# onV1.net
KiCad netlist of a schematic drawn in Altium Designer
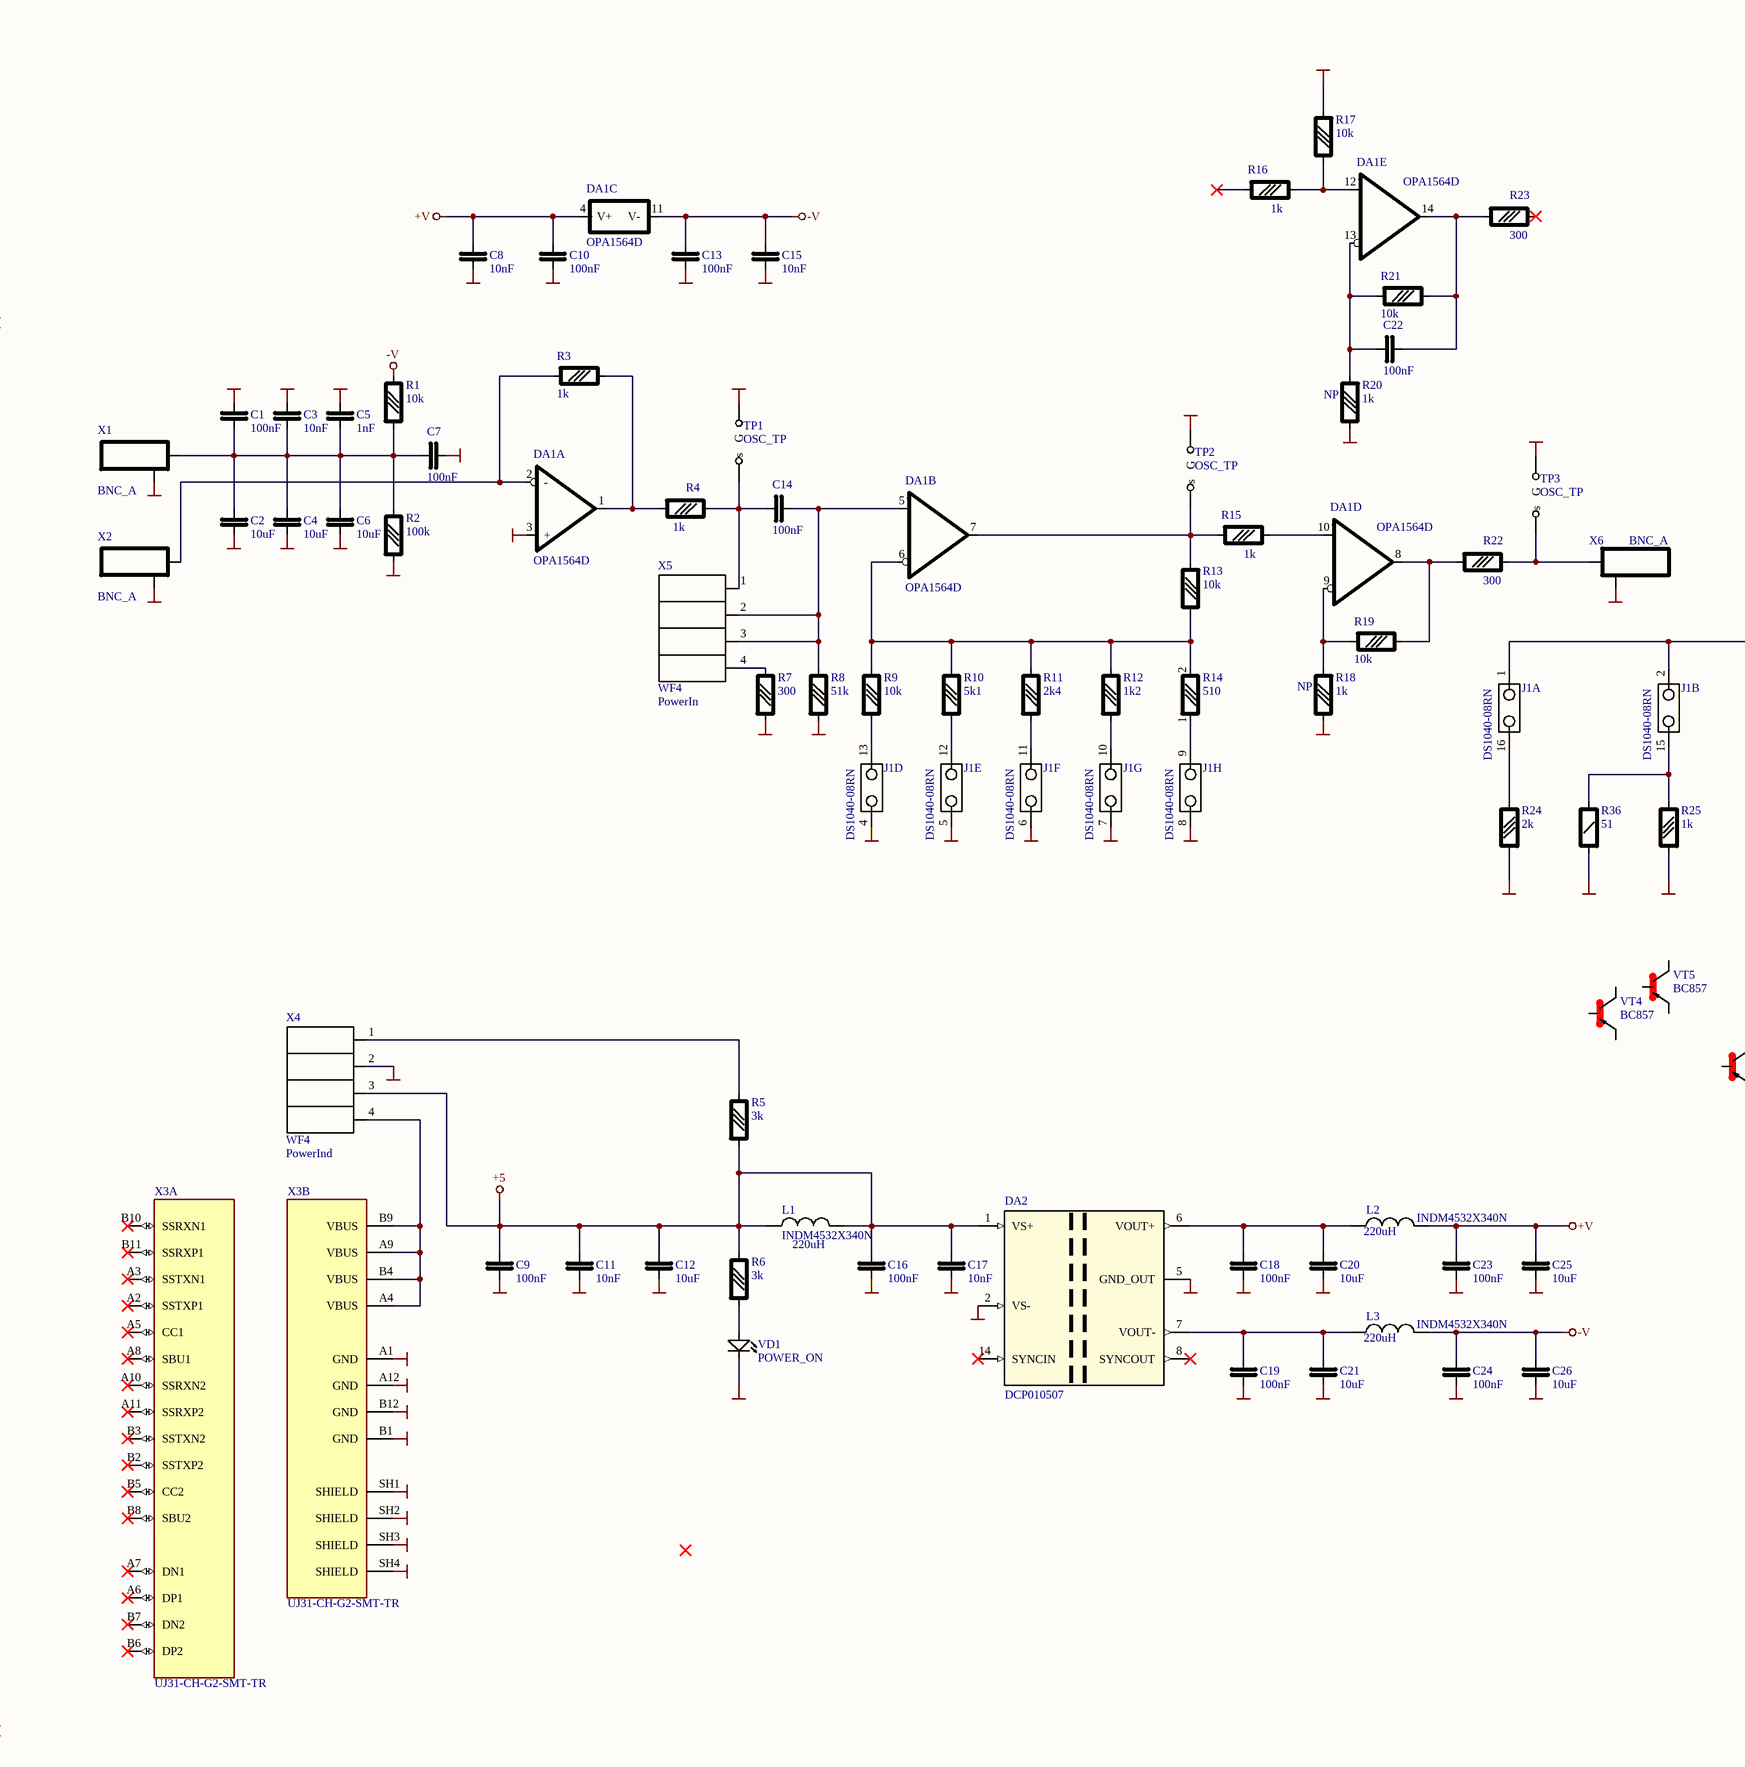
[diagram p0: onV1.SchDoc, left]
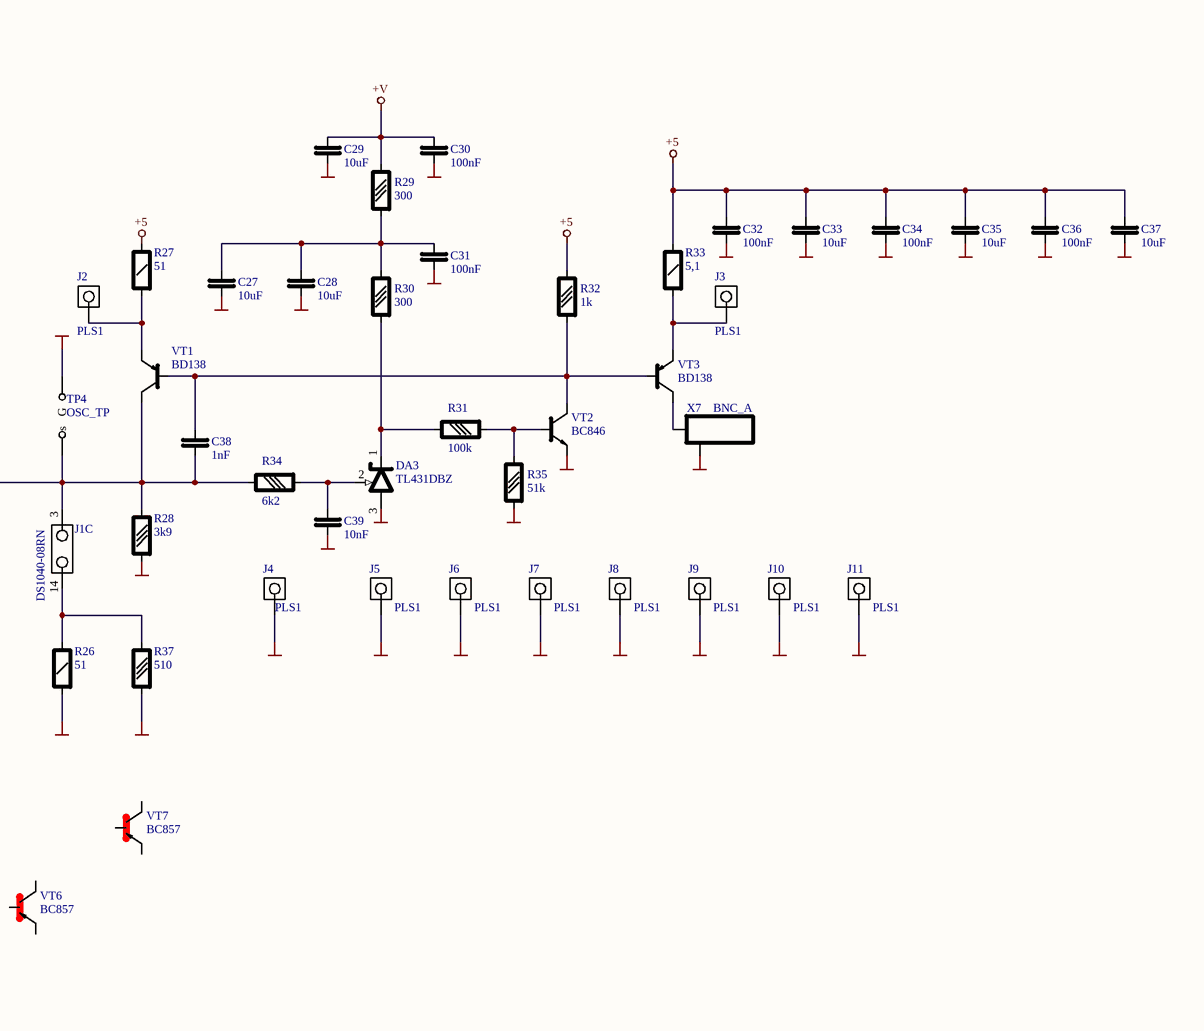
[diagram p1: onV1.SchDoc, right]

(export (version "E")
  (design (tool "Eeschema 10.0.6"))
  (components
    (comp (ref "C1")
      (value "100nF")
      (footprint "CAPC1608X87N")
      (description "Чип конденсатор 0603")
      (fields (field (name "VOLTAGE") "50V"))
      (libsource (lib "iL04_22") (part "C0603"))
    )
    (comp (ref "C2")
      (value "10uF")
      (footprint "SMD0805CAP")
      (description "Чип конденсатор 0805")
      (fields (field (name "VOLTAGE") "50V"))
      (libsource (lib "iL04_22") (part "C0805"))
    )
    (comp (ref "C3")
      (value "10nF")
      (footprint "CAPC1608X87N")
      (description "Чип конденсатор 0603")
      (fields (field (name "VOLTAGE") "50V"))
      (libsource (lib "iL04_22") (part "C0603"))
    )
    (comp (ref "C4")
      (value "10uF")
      (footprint "SMD0805CAP")
      (description "Чип конденсатор 0805")
      (fields (field (name "VOLTAGE") "50V"))
      (libsource (lib "iL04_22") (part "C0805"))
    )
    (comp (ref "C5")
      (value "1nF")
      (footprint "CAPC1608X87N")
      (description "Чип конденсатор 0603")
      (fields (field (name "VOLTAGE") "50V"))
      (libsource (lib "iL04_22") (part "C0603"))
    )
    (comp (ref "C6")
      (value "10uF")
      (footprint "SMD0805CAP")
      (description "Чип конденсатор 0805")
      (fields (field (name "VOLTAGE") "50V"))
      (libsource (lib "iL04_22") (part "C0805"))
    )
    (comp (ref "C7")
      (value "100nF")
      (footprint "CAPC1608X87N")
      (description "Чип конденсатор 0603")
      (fields (field (name "VOLTAGE") "50V"))
      (libsource (lib "iL04_22") (part "C0603"))
    )
    (comp (ref "C8")
      (value "10nF")
      (footprint "CAPC1608X87N")
      (description "Чип конденсатор 0603")
      (fields (field (name "VOLTAGE") "50V"))
      (libsource (lib "iL04_22") (part "C0603"))
    )
    (comp (ref "C9")
      (value "100nF")
      (footprint "CAPC1608X87N")
      (description "Чип конденсатор 0603")
      (fields (field (name "VOLTAGE") "50V"))
      (libsource (lib "iL04_22") (part "C0603"))
    )
    (comp (ref "C10")
      (value "100nF")
      (footprint "CAPC1608X87N")
      (description "Чип конденсатор 0603")
      (fields (field (name "VOLTAGE") "50V"))
      (libsource (lib "iL04_22") (part "C0603"))
    )
    (comp (ref "C11")
      (value "10nF")
      (footprint "CAPC1608X87N")
      (description "Чип конденсатор 0603")
      (fields (field (name "VOLTAGE") "50V"))
      (libsource (lib "iL04_22") (part "C0603"))
    )
    (comp (ref "C12")
      (value "10uF")
      (footprint "SMD0805CAP")
      (description "Чип конденсатор 0805")
      (fields (field (name "VOLTAGE") "50V"))
      (libsource (lib "iL04_22") (part "C0805"))
    )
    (comp (ref "C13")
      (value "100nF")
      (footprint "CAPC1608X87N")
      (description "Чип конденсатор 0603")
      (fields (field (name "VOLTAGE") "50V"))
      (libsource (lib "iL04_22") (part "C0603"))
    )
    (comp (ref "C14")
      (value "100nF")
      (footprint "CAPC1608X87N")
      (description "Чип конденсатор 0603")
      (fields (field (name "VOLTAGE") "50V"))
      (libsource (lib "iL04_22") (part "C0603"))
    )
    (comp (ref "C15")
      (value "10nF")
      (footprint "CAPC1608X87N")
      (description "Чип конденсатор 0603")
      (fields (field (name "VOLTAGE") "50V"))
      (libsource (lib "iL04_22") (part "C0603"))
    )
    (comp (ref "C16")
      (value "100nF")
      (footprint "CAPC1608X87N")
      (description "Чип конденсатор 0603")
      (fields (field (name "VOLTAGE") "50V"))
      (libsource (lib "iL04_22") (part "C0603"))
    )
    (comp (ref "C17")
      (value "10nF")
      (footprint "CAPC1608X87N")
      (description "Чип конденсатор 0603")
      (fields (field (name "VOLTAGE") "50V"))
      (libsource (lib "iL04_22") (part "C0603"))
    )
    (comp (ref "C18")
      (value "100nF")
      (footprint "CAPC1608X87N")
      (description "Чип конденсатор 0603")
      (fields (field (name "VOLTAGE") "50V"))
      (libsource (lib "iL04_22") (part "C0603"))
    )
    (comp (ref "C19")
      (value "100nF")
      (footprint "CAPC1608X87N")
      (description "Чип конденсатор 0603")
      (fields (field (name "VOLTAGE") "50V"))
      (libsource (lib "iL04_22") (part "C0603"))
    )
    (comp (ref "C20")
      (value "10uF")
      (footprint "SMD0805CAP")
      (description "Чип конденсатор 0805")
      (fields (field (name "VOLTAGE") "50V"))
      (libsource (lib "iL04_22") (part "C0805"))
    )
    (comp (ref "C21")
      (value "10uF")
      (footprint "SMD0805CAP")
      (description "Чип конденсатор 0805")
      (fields (field (name "VOLTAGE") "50V"))
      (libsource (lib "iL04_22") (part "C0805"))
    )
    (comp (ref "C22")
      (value "100nF")
      (footprint "CAPC1608X87N")
      (description "Чип конденсатор 0603")
      (fields (field (name "VOLTAGE") "50V"))
      (libsource (lib "iL04_22") (part "C0603"))
    )
    (comp (ref "C23")
      (value "100nF")
      (footprint "CAPC1608X87N")
      (description "Чип конденсатор 0603")
      (fields (field (name "VOLTAGE") "50V"))
      (libsource (lib "iL04_22") (part "C0603"))
    )
    (comp (ref "C24")
      (value "100nF")
      (footprint "CAPC1608X87N")
      (description "Чип конденсатор 0603")
      (fields (field (name "VOLTAGE") "50V"))
      (libsource (lib "iL04_22") (part "C0603"))
    )
    (comp (ref "C25")
      (value "10uF")
      (footprint "SMD0805CAP")
      (description "Чип конденсатор 0805")
      (fields (field (name "VOLTAGE") "50V"))
      (libsource (lib "iL04_22") (part "C0805"))
    )
    (comp (ref "C26")
      (value "10uF")
      (footprint "SMD0805CAP")
      (description "Чип конденсатор 0805")
      (fields (field (name "VOLTAGE") "50V"))
      (libsource (lib "iL04_22") (part "C0805"))
    )
    (comp (ref "C27")
      (value "10uF")
      (footprint "SMD0805CAP")
      (description "Чип конденсатор 0805")
      (fields (field (name "VOLTAGE") "50V"))
      (libsource (lib "iL04_22") (part "C0805"))
    )
    (comp (ref "C28")
      (value "10uF")
      (footprint "SMD0805CAP")
      (description "Чип конденсатор 0805")
      (fields (field (name "VOLTAGE") "50V"))
      (libsource (lib "iL04_22") (part "C0805"))
    )
    (comp (ref "C29")
      (value "10uF")
      (footprint "SMD0805CAP")
      (description "Чип конденсатор 0805")
      (fields (field (name "VOLTAGE") "50V"))
      (libsource (lib "iL04_22") (part "C0805"))
    )
    (comp (ref "C30")
      (value "100nF")
      (footprint "CAPC1608X87N")
      (description "Чип конденсатор 0603")
      (fields (field (name "VOLTAGE") "50V"))
      (libsource (lib "iL04_22") (part "C0603"))
    )
    (comp (ref "C31")
      (value "100nF")
      (footprint "CAPC1608X87N")
      (description "Чип конденсатор 0603")
      (fields (field (name "VOLTAGE") "50V"))
      (libsource (lib "iL04_22") (part "C0603"))
    )
    (comp (ref "C32")
      (value "100nF")
      (footprint "CAPC1608X87N")
      (description "Чип конденсатор 0603")
      (fields (field (name "VOLTAGE") "50V"))
      (libsource (lib "iL04_22") (part "C0603"))
    )
    (comp (ref "C33")
      (value "10uF")
      (footprint "SMD0805CAP")
      (description "Чип конденсатор 0805")
      (fields (field (name "VOLTAGE") "50V"))
      (libsource (lib "iL04_22") (part "C0805"))
    )
    (comp (ref "C34")
      (value "100nF")
      (footprint "CAPC1608X87N")
      (description "Чип конденсатор 0603")
      (fields (field (name "VOLTAGE") "50V"))
      (libsource (lib "iL04_22") (part "C0603"))
    )
    (comp (ref "C35")
      (value "10uF")
      (footprint "SMD0805CAP")
      (description "Чип конденсатор 0805")
      (fields (field (name "VOLTAGE") "50V"))
      (libsource (lib "iL04_22") (part "C0805"))
    )
    (comp (ref "C36")
      (value "100nF")
      (footprint "CAPC1608X87N")
      (description "Чип конденсатор 0603")
      (fields (field (name "VOLTAGE") "50V"))
      (libsource (lib "iL04_22") (part "C0603"))
    )
    (comp (ref "C37")
      (value "10uF")
      (footprint "SMD0805CAP")
      (description "Чип конденсатор 0805")
      (fields (field (name "VOLTAGE") "50V"))
      (libsource (lib "iL04_22") (part "C0805"))
    )
    (comp (ref "C38")
      (value "1nF")
      (footprint "CAPC1608X87N")
      (description "Чип конденсатор 0603")
      (fields (field (name "VOLTAGE") "50V"))
      (libsource (lib "iL04_22") (part "C0603"))
    )
    (comp (ref "C39")
      (value "10nF")
      (footprint "CAPC1608X87N")
      (description "Чип конденсатор 0603")
      (fields (field (name "VOLTAGE") "50V"))
      (libsource (lib "iL04_22") (part "C0603"))
    )
    (comp (ref "DA1")
      (value "OPA1564D")
      (footprint "SOIC14")
      (description "счетверённый ОУ JFED")
      (fields (field (name "VOLTAGE") "4.5V.. 36V/+-2.25..+-18V"))
      (libsource (lib "iL04_22") (part "OPA1564D"))
    )
    (comp (ref "DA2")
      (value "DCP010507")
      (footprint "NVA7")
      (description "DC/DC 5V to isolated +-7V")
      (fields (field (name "COPYRIGHT") "Copyright (C) 2022 Ultra Librarian. All rights reserved."))
      (libsource (lib "SL04_22F") (part "DCP010507"))
    )
    (comp (ref "DA3")
      (value "TL431DBZ")
      (footprint "SOT-23")
      (description "Adjustable voltage reference")
      (libsource (lib "SL04_22F") (part "TL431DBZ"))
    )
    (comp (ref "J1")
      (value "DS1040-08RN")
      (footprint "DIP16-300 W")
      (description "DIP переключатель 8x2.54")
      (libsource (lib "SL04_22F") (part "DS1040-08RN"))
    )
    (comp (ref "J2")
      (value "PLS1")
      (footprint "PLS1")
      (description "Штырь PLS1")
      (libsource (lib "iL04_22") (part "PLS1"))
    )
    (comp (ref "J3")
      (value "PLS1")
      (footprint "PLS1")
      (description "Штырь PLS1")
      (libsource (lib "iL04_22") (part "PLS1"))
    )
    (comp (ref "J4")
      (value "PLS1")
      (footprint "PLS1")
      (description "Штырь PLS1")
      (libsource (lib "iL04_22") (part "PLS1"))
    )
    (comp (ref "J5")
      (value "PLS1")
      (footprint "PLS1")
      (description "Штырь PLS1")
      (libsource (lib "iL04_22") (part "PLS1"))
    )
    (comp (ref "J6")
      (value "PLS1")
      (footprint "PLS1")
      (description "Штырь PLS1")
      (libsource (lib "iL04_22") (part "PLS1"))
    )
    (comp (ref "J7")
      (value "PLS1")
      (footprint "PLS1")
      (description "Штырь PLS1")
      (libsource (lib "iL04_22") (part "PLS1"))
    )
    (comp (ref "J8")
      (value "PLS1")
      (footprint "PLS1")
      (description "Штырь PLS1")
      (libsource (lib "iL04_22") (part "PLS1"))
    )
    (comp (ref "J9")
      (value "PLS1")
      (footprint "PLS1")
      (description "Штырь PLS1")
      (libsource (lib "iL04_22") (part "PLS1"))
    )
    (comp (ref "J10")
      (value "PLS1")
      (footprint "PLS1")
      (description "Штырь PLS1")
      (libsource (lib "iL04_22") (part "PLS1"))
    )
    (comp (ref "J11")
      (value "PLS1")
      (footprint "PLS1")
      (description "Штырь PLS1")
      (libsource (lib "iL04_22") (part "PLS1"))
    )
    (comp (ref "L1")
      (value "INDM4532X340N")
      (footprint "INDM4532X340N")
      (description "SMD Дроссель")
      (fields (field (name "INDUCTANCE") "220uH"))
      (libsource (lib "iL04_22") (part "INDM4532X340N"))
    )
    (comp (ref "L2")
      (value "INDM4532X340N")
      (footprint "INDM4532X340N")
      (description "SMD Дроссель")
      (fields (field (name "INDUCTANCE") "220uH"))
      (libsource (lib "iL04_22") (part "INDM4532X340N"))
    )
    (comp (ref "L3")
      (value "INDM4532X340N")
      (footprint "INDM4532X340N")
      (description "SMD Дроссель")
      (fields (field (name "INDUCTANCE") "220uH"))
      (libsource (lib "iL04_22") (part "INDM4532X340N"))
    )
    (comp (ref "R1")
      (value "10k")
      (footprint "RESC1608X64N")
      (description "Чип резистор 0603")
      (fields (field (name "TOLERANCE") "5%"))
      (libsource (lib "iL04_22") (part "R0603"))
    )
    (comp (ref "R2")
      (value "100k")
      (footprint "RESC1608X64N")
      (description "Чип резистор 0603")
      (fields (field (name "TOLERANCE") "5%"))
      (libsource (lib "iL04_22") (part "R0603"))
    )
    (comp (ref "R3")
      (value "1k")
      (footprint "RESC1608X64N")
      (description "Чип резистор 0603")
      (fields (field (name "TOLERANCE") "5%"))
      (libsource (lib "iL04_22") (part "R0603"))
    )
    (comp (ref "R4")
      (value "1k")
      (footprint "RESC1608X64N")
      (description "Чип резистор 0603")
      (fields (field (name "TOLERANCE") "5%"))
      (libsource (lib "iL04_22") (part "R0603"))
    )
    (comp (ref "R5")
      (value "3k")
      (footprint "RESC1608X64N")
      (description "Чип резистор 0603")
      (fields (field (name "TOLERANCE") "5%"))
      (libsource (lib "iL04_22") (part "R0603"))
    )
    (comp (ref "R6")
      (value "3k")
      (footprint "RESC1608X64N")
      (description "Чип резистор 0603")
      (fields (field (name "TOLERANCE") "5%"))
      (libsource (lib "iL04_22") (part "R0603"))
    )
    (comp (ref "R7")
      (value "300")
      (footprint "RESC1608X64N")
      (description "Чип резистор 0603")
      (fields (field (name "TOLERANCE") "5%"))
      (libsource (lib "iL04_22") (part "R0603"))
    )
    (comp (ref "R8")
      (value "51k")
      (footprint "RESC1608X64N")
      (description "Чип резистор 0603")
      (fields (field (name "TOLERANCE") "5%"))
      (libsource (lib "iL04_22") (part "R0603"))
    )
    (comp (ref "R9")
      (value "10k")
      (footprint "RESC1608X64N")
      (description "Чип резистор 0603")
      (fields (field (name "TOLERANCE") "5%"))
      (libsource (lib "iL04_22") (part "R0603"))
    )
    (comp (ref "R10")
      (value "5k1")
      (footprint "RESC1608X64N")
      (description "Чип резистор 0603")
      (fields (field (name "TOLERANCE") "5%"))
      (libsource (lib "iL04_22") (part "R0603"))
    )
    (comp (ref "R11")
      (value "2k4")
      (footprint "RESC1608X64N")
      (description "Чип резистор 0603")
      (fields (field (name "TOLERANCE") "5%"))
      (libsource (lib "iL04_22") (part "R0603"))
    )
    (comp (ref "R12")
      (value "1k2")
      (footprint "RESC1608X64N")
      (description "Чип резистор 0603")
      (fields (field (name "TOLERANCE") "5%"))
      (libsource (lib "iL04_22") (part "R0603"))
    )
    (comp (ref "R13")
      (value "10k")
      (footprint "RESC1608X64N")
      (description "Чип резистор 0603")
      (fields (field (name "TOLERANCE") "5%"))
      (libsource (lib "iL04_22") (part "R0603"))
    )
    (comp (ref "R14")
      (value "510")
      (footprint "RESC1608X64N")
      (description "Чип резистор 0603")
      (fields (field (name "TOLERANCE") "5%"))
      (libsource (lib "") (part "R0603_1"))
    )
    (comp (ref "R15")
      (value "1k")
      (footprint "RESC1608X64N")
      (description "Чип резистор 0603")
      (fields (field (name "TOLERANCE") "5%"))
      (libsource (lib "iL04_22") (part "R0603"))
    )
    (comp (ref "R16")
      (value "1k")
      (footprint "RESC1608X64N")
      (description "Чип резистор 0603")
      (fields (field (name "TOLERANCE") "5%"))
      (libsource (lib "iL04_22") (part "R0603"))
    )
    (comp (ref "R17")
      (value "10k")
      (footprint "RESC1608X64N")
      (description "Чип резистор 0603")
      (fields (field (name "TOLERANCE") "5%"))
      (libsource (lib "iL04_22") (part "R0603"))
    )
    (comp (ref "R18")
      (value "1k")
      (footprint "RESC1608X64N")
      (description "Чип резистор 0603")
      (fields (field (name "TOLERANCE") "5%") (field (name "SOLDEROPTION") "NP"))
      (libsource (lib "iL04_22") (part "R0603"))
    )
    (comp (ref "R19")
      (value "10k")
      (footprint "RESC1608X64N")
      (description "Чип резистор 0603")
      (fields (field (name "TOLERANCE") "5%"))
      (libsource (lib "iL04_22") (part "R0603"))
    )
    (comp (ref "R20")
      (value "1k")
      (footprint "RESC1608X64N")
      (description "Чип резистор 0603")
      (fields (field (name "TOLERANCE") "5%") (field (name "SOLDEROPTION") "NP"))
      (libsource (lib "iL04_22") (part "R0603"))
    )
    (comp (ref "R21")
      (value "10k")
      (footprint "RESC1608X64N")
      (description "Чип резистор 0603")
      (fields (field (name "TOLERANCE") "5%"))
      (libsource (lib "iL04_22") (part "R0603"))
    )
    (comp (ref "R22")
      (value "300")
      (footprint "RESC1608X64N")
      (description "Чип резистор 0603")
      (fields (field (name "TOLERANCE") "5%"))
      (libsource (lib "iL04_22") (part "R0603"))
    )
    (comp (ref "R23")
      (value "300")
      (footprint "RESC1608X64N")
      (description "Чип резистор 0603")
      (fields (field (name "TOLERANCE") "5%"))
      (libsource (lib "iL04_22") (part "R0603"))
    )
    (comp (ref "R24")
      (value "2k")
      (footprint "RESC1608X64N")
      (description "Чип резистор 0603")
      (fields (field (name "TOLERANCE") "5%"))
      (libsource (lib "iL04_22") (part "R0603"))
    )
    (comp (ref "R25")
      (value "1k")
      (footprint "RESC1608X64N")
      (description "Чип резистор 0603")
      (fields (field (name "TOLERANCE") "5%"))
      (libsource (lib "iL04_22") (part "R0603"))
    )
    (comp (ref "R26")
      (value "51")
      (footprint "RES1206")
      (description "Чип резистор 1206")
      (fields (field (name "TOLERANCE") "5%"))
      (libsource (lib "iL04_22") (part "R1206"))
    )
    (comp (ref "R27")
      (value "51")
      (footprint "RES1206")
      (description "Чип резистор 1206")
      (fields (field (name "TOLERANCE") "5%"))
      (libsource (lib "iL04_22") (part "R1206"))
    )
    (comp (ref "R28")
      (value "3k9")
      (footprint "RESC1608X64N")
      (description "Чип резистор 0603")
      (fields (field (name "TOLERANCE") "5%"))
      (libsource (lib "iL04_22") (part "R0603"))
    )
    (comp (ref "R29")
      (value "300")
      (footprint "RESC1608X64N")
      (description "Чип резистор 0603")
      (fields (field (name "TOLERANCE") "5%"))
      (libsource (lib "iL04_22") (part "R0603"))
    )
    (comp (ref "R30")
      (value "300")
      (footprint "RESC1608X64N")
      (description "Чип резистор 0603")
      (fields (field (name "TOLERANCE") "5%"))
      (libsource (lib "iL04_22") (part "R0603"))
    )
    (comp (ref "R31")
      (value "100k")
      (footprint "RESC1608X64N")
      (description "Чип резистор 0603")
      (fields (field (name "TOLERANCE") "5%"))
      (libsource (lib "iL04_22") (part "R0603"))
    )
    (comp (ref "R32")
      (value "1k")
      (footprint "RESC1608X64N")
      (description "Чип резистор 0603")
      (fields (field (name "TOLERANCE") "5%"))
      (libsource (lib "iL04_22") (part "R0603"))
    )
    (comp (ref "R33")
      (value "5,1")
      (footprint "RES1206")
      (description "Чип резистор 1206")
      (fields (field (name "TOLERANCE") "5%"))
      (libsource (lib "iL04_22") (part "R1206"))
    )
    (comp (ref "R34")
      (value "6k2")
      (footprint "RESC1608X64N")
      (description "Чип резистор 0603")
      (fields (field (name "TOLERANCE") "5%"))
      (libsource (lib "iL04_22") (part "R0603"))
    )
    (comp (ref "R35")
      (value "51k")
      (footprint "RESC1608X64N")
      (description "Чип резистор 0603")
      (fields (field (name "TOLERANCE") "5%"))
      (libsource (lib "iL04_22") (part "R0603"))
    )
    (comp (ref "R36")
      (value "51")
      (footprint "RES1206")
      (description "Чип резистор 1206")
      (fields (field (name "TOLERANCE") "5%"))
      (libsource (lib "iL04_22") (part "R1206"))
    )
    (comp (ref "R37")
      (value "510")
      (footprint "RESC1608X64N")
      (description "Чип резистор 0603")
      (fields (field (name "TOLERANCE") "5%"))
      (libsource (lib "iL04_22") (part "R0603"))
    )
    (comp (ref "TP1")
      (value "OSC_TP")
      (footprint "TP2")
      (description "Контрольная точка для подключения осциллографа короткой землёй")
      (libsource (lib "iL04_22") (part "OscTP"))
    )
    (comp (ref "TP2")
      (value "OSC_TP")
      (footprint "TP2")
      (description "Контрольная точка для подключения осциллографа короткой землёй")
      (libsource (lib "iL04_22") (part "OscTP"))
    )
    (comp (ref "TP3")
      (value "OSC_TP")
      (footprint "TP2")
      (description "Контрольная точка для подключения осциллографа короткой землёй")
      (libsource (lib "iL04_22") (part "OscTP"))
    )
    (comp (ref "TP4")
      (value "OSC_TP")
      (footprint "TP2")
      (description "Контрольная точка для подключения осциллографа короткой землёй")
      (libsource (lib "iL04_22") (part "OscTP"))
    )
    (comp (ref "VD1")
      (value "POWER_ON")
      (footprint "LED0603")
      (description "Чип светодиод 0603")
      (libsource (lib "iL04_22") (part "LED0603"))
    )
    (comp (ref "VT1")
      (value "BD138")
      (footprint "TO229P780X300X1364-3")
      (description "PNP  средней мощности (КГ814)")
      (fields (field (name "VOLTAGE") "40-100"))
      (libsource (lib "iL04_22") (part "BD138"))
    )
    (comp (ref "VT2")
      (value "BC846")
      (footprint "SOT-23")
      (description "NPN транзистор")
      (fields (field (name "VOLTAGE") "65V"))
      (libsource (lib "iL04_22") (part "BC846"))
    )
    (comp (ref "VT3")
      (value "BD138")
      (footprint "TO229P780X300X1364-3")
      (description "PNP  средней мощности (КГ814)")
      (fields (field (name "VOLTAGE") "40-100"))
      (libsource (lib "iL04_22") (part "BD138"))
    )
    (comp (ref "VT4")
      (value "BC857")
      (footprint "SOT-23")
      (description "PNP транзистор")
      (fields (field (name "VOLTAGE") "65V"))
      (libsource (lib "SL04_22F") (part "BC857"))
    )
    (comp (ref "VT5")
      (value "BC857")
      (footprint "SOT-23")
      (description "PNP транзистор")
      (fields (field (name "VOLTAGE") "65V"))
      (libsource (lib "SL04_22F") (part "BC857"))
    )
    (comp (ref "VT6")
      (value "BC857")
      (footprint "SOT-23")
      (description "PNP транзистор")
      (fields (field (name "VOLTAGE") "65V"))
      (libsource (lib "SL04_22F") (part "BC857"))
    )
    (comp (ref "VT7")
      (value "BC857")
      (footprint "SOT-23")
      (description "PNP транзистор")
      (fields (field (name "VOLTAGE") "65V"))
      (libsource (lib "SL04_22F") (part "BC857"))
    )
    (comp (ref "X1")
      (value "BNC_A")
      (footprint "TYCO_1-1337542-0")
      (description "BNC розетка")
      (fields (field (name "PARTNUM") "TYCO_1-1337542-0"))
      (libsource (lib "iL04_22") (part "BNC_A"))
    )
    (comp (ref "X2")
      (value "BNC_A")
      (footprint "TYCO_1-1337542-0")
      (description "BNC розетка")
      (fields (field (name "PARTNUM") "TYCO_1-1337542-0"))
      (libsource (lib "iL04_22") (part "BNC_A"))
    )
    (comp (ref "X3")
      (value "UJ31-CH-G2-SMT-TR")
      (footprint "CUI_UJ31-CH-G2-SMT-TR")
      (description "Type C, USB 3.1 Gen 2, 5 A, Right Angle, Surface Mount (SMT), USB Receptacle")
      (fields (field (name "MF") "CUI Devices"))
      (libsource (lib "SL04_22F") (part "UJ31-CH-G2-SMT-TR"))
    )
    (comp (ref "X4")
      (value "WF4")
      (footprint "MOLEX_22-27-2041")
      (description "Вилка  WF4x2.54")
      (fields (field (name "CONNECTTO") "PowerInd"))
      (libsource (lib "iL04_22") (part "WF4"))
    )
    (comp (ref "X5")
      (value "WF4")
      (footprint "MOLEX_22-27-2041")
      (description "Вилка  WF4x2.54")
      (fields (field (name "CONNECTTO") "PowerIn"))
      (libsource (lib "iL04_22") (part "WF4"))
    )
    (comp (ref "X6")
      (value "BNC_A")
      (footprint "TYCO_1-1337542-0")
      (description "BNC розетка")
      (fields (field (name "PARTNUM") "TYCO_1-1337542-0"))
      (libsource (lib "iL04_22") (part "BNC_A"))
    )
    (comp (ref "X7")
      (value "BNC_A")
      (footprint "TYCO_1-1337542-0")
      (description "BNC розетка")
      (fields (field (name "PARTNUM") "TYCO_1-1337542-0"))
      (libsource (lib "iL04_22") (part "BNC_A"))
    )
  )
  (nets
    (net (code "1") (name "+5") (class "Default")
      (node (ref "C11") (pin "2") (pinfunction "2_2") (pintype "passive"))
      (node (ref "C12") (pin "2") (pinfunction "2_2") (pintype "passive"))
      (node (ref "C16") (pin "2") (pinfunction "2_2") (pintype "passive"))
      (node (ref "C17") (pin "2") (pinfunction "2_2") (pintype "passive"))
      (node (ref "C32") (pin "2") (pinfunction "2_2") (pintype "passive"))
      (node (ref "C33") (pin "2") (pinfunction "2_2") (pintype "passive"))
      (node (ref "C34") (pin "2") (pinfunction "2_2") (pintype "passive"))
      (node (ref "C35") (pin "2") (pinfunction "2_2") (pintype "passive"))
      (node (ref "C36") (pin "2") (pinfunction "2_2") (pintype "passive"))
      (node (ref "C37") (pin "2") (pinfunction "2_2") (pintype "passive"))
      (node (ref "C9") (pin "2") (pinfunction "2_2") (pintype "passive"))
      (node (ref "DA2") (pin "1") (pinfunction "VS+_1") (pintype "input"))
      (node (ref "L1") (pin "1") (pinfunction "1_1") (pintype "passive"))
      (node (ref "L1") (pin "2") (pinfunction "2_2") (pintype "passive"))
      (node (ref "R27") (pin "2") (pinfunction "2_2") (pintype "passive"))
      (node (ref "R32") (pin "2") (pinfunction "2_2") (pintype "passive"))
      (node (ref "R33") (pin "2") (pinfunction "2_2") (pintype "passive"))
      (node (ref "R5") (pin "1") (pinfunction "1_1") (pintype "passive"))
      (node (ref "R6") (pin "2") (pinfunction "2_2") (pintype "passive"))
      (node (ref "X4") (pin "3") (pinfunction "3_3") (pintype "passive"))
    )
    (net (code "2") (name "+V") (class "Default")
      (node (ref "C10") (pin "2") (pinfunction "2_2") (pintype "passive"))
      (node (ref "C23") (pin "2") (pinfunction "2_2") (pintype "passive"))
      (node (ref "C25") (pin "2") (pinfunction "2_2") (pintype "passive"))
      (node (ref "C29") (pin "2") (pinfunction "2_2") (pintype "passive"))
      (node (ref "C30") (pin "2") (pinfunction "2_2") (pintype "passive"))
      (node (ref "C8") (pin "2") (pinfunction "2_2") (pintype "passive"))
      (node (ref "DA1") (pin "4") (pinfunction "V+_4") (pintype "power_in"))
      (node (ref "L2") (pin "2") (pinfunction "2_2") (pintype "passive"))
      (node (ref "R29") (pin "2") (pinfunction "2_2") (pintype "passive"))
    )
    (net (code "3") (name "-V") (class "Default")
      (node (ref "C13") (pin "2") (pinfunction "2_2") (pintype "passive"))
      (node (ref "C15") (pin "2") (pinfunction "2_2") (pintype "passive"))
      (node (ref "C24") (pin "2") (pinfunction "2_2") (pintype "passive"))
      (node (ref "C26") (pin "2") (pinfunction "2_2") (pintype "passive"))
      (node (ref "DA1") (pin "11") (pinfunction "V-_11") (pintype "power_in"))
      (node (ref "L3") (pin "2") (pinfunction "2_2") (pintype "passive"))
      (node (ref "R1") (pin "2") (pinfunction "2_2") (pintype "passive"))
    )
    (net (code "4") (name "GND") (class "Default")
      (node (ref "C1") (pin "2") (pinfunction "2_2") (pintype "passive"))
      (node (ref "C10") (pin "1") (pinfunction "1_1") (pintype "passive"))
      (node (ref "C11") (pin "1") (pinfunction "1_1") (pintype "passive"))
      (node (ref "C12") (pin "1") (pinfunction "1_1") (pintype "passive"))
      (node (ref "C13") (pin "1") (pinfunction "1_1") (pintype "passive"))
      (node (ref "C15") (pin "1") (pinfunction "1_1") (pintype "passive"))
      (node (ref "C16") (pin "1") (pinfunction "1_1") (pintype "passive"))
      (node (ref "C17") (pin "1") (pinfunction "1_1") (pintype "passive"))
      (node (ref "C18") (pin "1") (pinfunction "1_1") (pintype "passive"))
      (node (ref "C19") (pin "1") (pinfunction "1_1") (pintype "passive"))
      (node (ref "C2") (pin "1") (pinfunction "1_1") (pintype "passive"))
      (node (ref "C20") (pin "1") (pinfunction "1_1") (pintype "passive"))
      (node (ref "C21") (pin "1") (pinfunction "1_1") (pintype "passive"))
      (node (ref "C23") (pin "1") (pinfunction "1_1") (pintype "passive"))
      (node (ref "C24") (pin "1") (pinfunction "1_1") (pintype "passive"))
      (node (ref "C25") (pin "1") (pinfunction "1_1") (pintype "passive"))
      (node (ref "C26") (pin "1") (pinfunction "1_1") (pintype "passive"))
      (node (ref "C27") (pin "1") (pinfunction "1_1") (pintype "passive"))
      (node (ref "C28") (pin "1") (pinfunction "1_1") (pintype "passive"))
      (node (ref "C29") (pin "1") (pinfunction "1_1") (pintype "passive"))
      (node (ref "C3") (pin "2") (pinfunction "2_2") (pintype "passive"))
      (node (ref "C30") (pin "1") (pinfunction "1_1") (pintype "passive"))
      (node (ref "C31") (pin "1") (pinfunction "1_1") (pintype "passive"))
      (node (ref "C32") (pin "1") (pinfunction "1_1") (pintype "passive"))
      (node (ref "C33") (pin "1") (pinfunction "1_1") (pintype "passive"))
      (node (ref "C34") (pin "1") (pinfunction "1_1") (pintype "passive"))
      (node (ref "C35") (pin "1") (pinfunction "1_1") (pintype "passive"))
      (node (ref "C36") (pin "1") (pinfunction "1_1") (pintype "passive"))
      (node (ref "C37") (pin "1") (pinfunction "1_1") (pintype "passive"))
      (node (ref "C39") (pin "1") (pinfunction "1_1") (pintype "passive"))
      (node (ref "C4") (pin "1") (pinfunction "1_1") (pintype "passive"))
      (node (ref "C5") (pin "2") (pinfunction "2_2") (pintype "passive"))
      (node (ref "C6") (pin "1") (pinfunction "1_1") (pintype "passive"))
      (node (ref "C7") (pin "2") (pinfunction "2_2") (pintype "passive"))
      (node (ref "C8") (pin "1") (pinfunction "1_1") (pintype "passive"))
      (node (ref "C9") (pin "1") (pinfunction "1_1") (pintype "passive"))
      (node (ref "DA1") (pin "3") (pinfunction "+_3") (pintype "input"))
      (node (ref "DA2") (pin "2") (pinfunction "VS-_2") (pintype "input"))
      (node (ref "DA2") (pin "5") (pinfunction "GND_OUT_5") (pintype "power_in"))
      (node (ref "DA3") (pin "3") (pinfunction "A_3") (pintype "passive"))
      (node (ref "J1") (pin "4") (pinfunction "4_4") (pintype "passive"))
      (node (ref "J1") (pin "5") (pinfunction "5_5") (pintype "passive"))
      (node (ref "J1") (pin "6") (pinfunction "6_6") (pintype "passive"))
      (node (ref "J1") (pin "7") (pinfunction "7_7") (pintype "passive"))
      (node (ref "J1") (pin "8") (pinfunction "8_8") (pintype "passive"))
      (node (ref "J10") (pin "1") (pinfunction "1_1") (pintype "passive"))
      (node (ref "J11") (pin "1") (pinfunction "1_1") (pintype "passive"))
      (node (ref "J4") (pin "1") (pinfunction "1_1") (pintype "passive"))
      (node (ref "J5") (pin "1") (pinfunction "1_1") (pintype "passive"))
      (node (ref "J6") (pin "1") (pinfunction "1_1") (pintype "passive"))
      (node (ref "J7") (pin "1") (pinfunction "1_1") (pintype "passive"))
      (node (ref "J8") (pin "1") (pinfunction "1_1") (pintype "passive"))
      (node (ref "J9") (pin "1") (pinfunction "1_1") (pintype "passive"))
      (node (ref "R17") (pin "1") (pinfunction "1_1") (pintype "passive"))
      (node (ref "R18") (pin "2") (pinfunction "2_2") (pintype "passive"))
      (node (ref "R2") (pin "1") (pinfunction "1_1") (pintype "passive"))
      (node (ref "R20") (pin "2") (pinfunction "2_2") (pintype "passive"))
      (node (ref "R24") (pin "1") (pinfunction "1_1") (pintype "passive"))
      (node (ref "R25") (pin "1") (pinfunction "1_1") (pintype "passive"))
      (node (ref "R26") (pin "1") (pinfunction "1_1") (pintype "passive"))
      (node (ref "R28") (pin "1") (pinfunction "1_1") (pintype "passive"))
      (node (ref "R35") (pin "1") (pinfunction "1_1") (pintype "passive"))
      (node (ref "R36") (pin "1") (pinfunction "1_1") (pintype "passive"))
      (node (ref "R37") (pin "1") (pinfunction "1_1") (pintype "passive"))
      (node (ref "R7") (pin "1") (pinfunction "1_1") (pintype "passive"))
      (node (ref "R8") (pin "1") (pinfunction "1_1") (pintype "passive"))
      (node (ref "TP1") (pin "2") (pinfunction "G_2") (pintype "passive"))
      (node (ref "TP2") (pin "2") (pinfunction "G_2") (pintype "passive"))
      (node (ref "TP3") (pin "2") (pinfunction "G_2") (pintype "passive"))
      (node (ref "TP4") (pin "2") (pinfunction "G_2") (pintype "passive"))
      (node (ref "VD1") (pin "1") (pinfunction "Cathode_1") (pintype "passive"))
      (node (ref "VT2") (pin "2") (pinfunction "Emitter_2") (pintype "passive"))
      (node (ref "X1") (pin "2") (pinfunction "2_2") (pintype "passive"))
      (node (ref "X2") (pin "2") (pinfunction "2_2") (pintype "passive"))
      (node (ref "X3") (pin "A1") (pinfunction "GND_A1") (pintype "power_in"))
      (node (ref "X3") (pin "A12") (pinfunction "GND_A12") (pintype "power_in"))
      (node (ref "X3") (pin "B1") (pinfunction "GND_B1") (pintype "power_in"))
      (node (ref "X3") (pin "B12") (pinfunction "GND_B12") (pintype "power_in"))
      (node (ref "X3") (pin "SH1") (pinfunction "SHIELD_SH1") (pintype "power_in"))
      (node (ref "X3") (pin "SH2") (pinfunction "SHIELD_SH2") (pintype "power_in"))
      (node (ref "X3") (pin "SH3") (pinfunction "SHIELD_SH3") (pintype "power_in"))
      (node (ref "X3") (pin "SH4") (pinfunction "SHIELD_SH4") (pintype "power_in"))
      (node (ref "X4") (pin "2") (pinfunction "2_2") (pintype "passive"))
      (node (ref "X6") (pin "2") (pinfunction "2_2") (pintype "passive"))
      (node (ref "X7") (pin "2") (pinfunction "2_2") (pintype "passive"))
    )
    (net (code "5") (name "Net-(C1-Pad1)") (class "Default")
      (node (ref "C1") (pin "1") (pinfunction "1_1") (pintype "passive"))
      (node (ref "C2") (pin "2") (pinfunction "2_2") (pintype "passive"))
      (node (ref "C3") (pin "1") (pinfunction "1_1") (pintype "passive"))
      (node (ref "C4") (pin "2") (pinfunction "2_2") (pintype "passive"))
      (node (ref "C5") (pin "1") (pinfunction "1_1") (pintype "passive"))
      (node (ref "C6") (pin "2") (pinfunction "2_2") (pintype "passive"))
      (node (ref "C7") (pin "1") (pinfunction "1_1") (pintype "passive"))
      (node (ref "R1") (pin "1") (pinfunction "1_1") (pintype "passive"))
      (node (ref "R2") (pin "2") (pinfunction "2_2") (pintype "passive"))
      (node (ref "X1") (pin "1") (pinfunction "1_1") (pintype "passive"))
    )
    (net (code "6") (name "Net-(C27-Pad2)") (class "Default")
      (node (ref "C27") (pin "2") (pinfunction "2_2") (pintype "passive"))
      (node (ref "C28") (pin "2") (pinfunction "2_2") (pintype "passive"))
      (node (ref "C31") (pin "2") (pinfunction "2_2") (pintype "passive"))
      (node (ref "R29") (pin "1") (pinfunction "1_1") (pintype "passive"))
      (node (ref "R30") (pin "2") (pinfunction "2_2") (pintype "passive"))
    )
    (net (code "7") (name "Net-(DA1A--)") (class "Default")
      (node (ref "DA1") (pin "2") (pinfunction "-_2") (pintype "input"))
      (node (ref "R3") (pin "1") (pinfunction "1_1") (pintype "passive"))
      (node (ref "X2") (pin "1") (pinfunction "1_1") (pintype "passive"))
    )
    (net (code "8") (name "Net-(DA1A-OUT)") (class "Default")
      (node (ref "DA1") (pin "1") (pinfunction "OUT_1") (pintype "output"))
      (node (ref "R3") (pin "2") (pinfunction "2_2") (pintype "passive"))
      (node (ref "R4") (pin "1") (pinfunction "1_1") (pintype "passive"))
    )
    (net (code "9") (name "Net-(DA1B-+)") (class "Default")
      (node (ref "C14") (pin "2") (pinfunction "2_2") (pintype "passive"))
      (node (ref "DA1") (pin "5") (pinfunction "+_5") (pintype "input"))
      (node (ref "R8") (pin "2") (pinfunction "2_2") (pintype "passive"))
      (node (ref "X5") (pin "2") (pinfunction "2_2") (pintype "passive"))
      (node (ref "X5") (pin "3") (pinfunction "3_3") (pintype "passive"))
    )
    (net (code "10") (name "Net-(DA1B--)") (class "Default")
      (node (ref "DA1") (pin "6") (pinfunction "-_6") (pintype "passive"))
      (node (ref "R10") (pin "2") (pinfunction "2_2") (pintype "passive"))
      (node (ref "R11") (pin "2") (pinfunction "2_2") (pintype "passive"))
      (node (ref "R12") (pin "2") (pinfunction "2_2") (pintype "passive"))
      (node (ref "R13") (pin "2") (pinfunction "2_2") (pintype "passive"))
      (node (ref "R14") (pin "2") (pinfunction "2_2") (pintype "passive"))
      (node (ref "R9") (pin "2") (pinfunction "2_2") (pintype "passive"))
    )
    (net (code "11") (name "Net-(DA1B-OUT)") (class "Default")
      (node (ref "DA1") (pin "7") (pinfunction "OUT_7") (pintype "passive"))
      (node (ref "R13") (pin "1") (pinfunction "1_1") (pintype "passive"))
      (node (ref "R15") (pin "1") (pinfunction "1_1") (pintype "passive"))
      (node (ref "TP2") (pin "1") (pinfunction "s_1") (pintype "passive"))
    )
    (net (code "12") (name "Net-(DA1D-+)") (class "Default")
      (node (ref "DA1") (pin "10") (pinfunction "+_10") (pintype "input"))
      (node (ref "R15") (pin "2") (pinfunction "2_2") (pintype "passive"))
    )
    (net (code "13") (name "Net-(DA1D--)") (class "Default")
      (node (ref "DA1") (pin "9") (pinfunction "-_9") (pintype "passive"))
      (node (ref "R18") (pin "1") (pinfunction "1_1") (pintype "passive"))
      (node (ref "R19") (pin "1") (pinfunction "1_1") (pintype "passive"))
    )
    (net (code "14") (name "Net-(DA1D-OUT)") (class "Default")
      (node (ref "DA1") (pin "8") (pinfunction "OUT_8") (pintype "passive"))
      (node (ref "R19") (pin "2") (pinfunction "2_2") (pintype "passive"))
      (node (ref "R22") (pin "1") (pinfunction "1_1") (pintype "passive"))
    )
    (net (code "15") (name "Net-(DA1E-+)") (class "Default")
      (node (ref "DA1") (pin "12") (pinfunction "+_12") (pintype "input"))
      (node (ref "R16") (pin "2") (pinfunction "2_2") (pintype "passive"))
      (node (ref "R17") (pin "2") (pinfunction "2_2") (pintype "passive"))
    )
    (net (code "16") (name "Net-(DA1E--)") (class "Default")
      (node (ref "C22") (pin "1") (pinfunction "1_1") (pintype "passive"))
      (node (ref "DA1") (pin "13") (pinfunction "-_13") (pintype "passive"))
      (node (ref "R20") (pin "1") (pinfunction "1_1") (pintype "passive"))
      (node (ref "R21") (pin "1") (pinfunction "1_1") (pintype "passive"))
    )
    (net (code "17") (name "Net-(DA1E-OUT)") (class "Default")
      (node (ref "C22") (pin "2") (pinfunction "2_2") (pintype "passive"))
      (node (ref "DA1") (pin "14") (pinfunction "OUT_14") (pintype "passive"))
      (node (ref "R21") (pin "2") (pinfunction "2_2") (pintype "passive"))
      (node (ref "R23") (pin "1") (pinfunction "1_1") (pintype "passive"))
    )
    (net (code "18") (name "Net-(DA2-VOUT+)") (class "Default")
      (node (ref "C18") (pin "2") (pinfunction "2_2") (pintype "passive"))
      (node (ref "C20") (pin "2") (pinfunction "2_2") (pintype "passive"))
      (node (ref "DA2") (pin "6") (pinfunction "VOUT+_6") (pintype "output"))
      (node (ref "L2") (pin "1") (pinfunction "1_1") (pintype "passive"))
    )
    (net (code "19") (name "Net-(DA2-VOUT-)") (class "Default")
      (node (ref "C19") (pin "2") (pinfunction "2_2") (pintype "passive"))
      (node (ref "C21") (pin "2") (pinfunction "2_2") (pintype "passive"))
      (node (ref "DA2") (pin "7") (pinfunction "VOUT-_7") (pintype "output"))
      (node (ref "L3") (pin "1") (pinfunction "1_1") (pintype "passive"))
    )
    (net (code "20") (name "Net-(DA3-C)") (class "Default")
      (node (ref "DA3") (pin "1") (pinfunction "C_1") (pintype "passive"))
      (node (ref "R30") (pin "1") (pinfunction "1_1") (pintype "passive"))
      (node (ref "R31") (pin "2") (pinfunction "2_2") (pintype "passive"))
    )
    (net (code "21") (name "Net-(DA3-Ref)") (class "Default")
      (node (ref "C39") (pin "2") (pinfunction "2_2") (pintype "passive"))
      (node (ref "DA3") (pin "2") (pinfunction "Ref_2") (pintype "input"))
      (node (ref "R34") (pin "1") (pinfunction "1_1") (pintype "passive"))
    )
    (net (code "22") (name "Net-(J1-Pad9)") (class "Default")
      (node (ref "J1") (pin "9") (pinfunction "9_9") (pintype "passive"))
      (node (ref "R14") (pin "1") (pinfunction "1_1") (pintype "passive"))
    )
    (net (code "23") (name "Net-(J1-Pad10)") (class "Default")
      (node (ref "J1") (pin "10") (pinfunction "10_10") (pintype "passive"))
      (node (ref "R12") (pin "1") (pinfunction "1_1") (pintype "passive"))
    )
    (net (code "24") (name "Net-(J1-Pad11)") (class "Default")
      (node (ref "J1") (pin "11") (pinfunction "11_11") (pintype "passive"))
      (node (ref "R11") (pin "1") (pinfunction "1_1") (pintype "passive"))
    )
    (net (code "25") (name "Net-(J1-Pad12)") (class "Default")
      (node (ref "J1") (pin "12") (pinfunction "12_12") (pintype "passive"))
      (node (ref "R10") (pin "1") (pinfunction "1_1") (pintype "passive"))
    )
    (net (code "26") (name "Net-(J1-Pad13)") (class "Default")
      (node (ref "J1") (pin "13") (pinfunction "13_13") (pintype "passive"))
      (node (ref "R9") (pin "1") (pinfunction "1_1") (pintype "passive"))
    )
    (net (code "27") (name "Net-(J1-Pad14)") (class "Default")
      (node (ref "J1") (pin "14") (pinfunction "14_14") (pintype "passive"))
      (node (ref "R26") (pin "2") (pinfunction "2_2") (pintype "passive"))
      (node (ref "R37") (pin "2") (pinfunction "2_2") (pintype "passive"))
    )
    (net (code "28") (name "Net-(J1-Pad15)") (class "Default")
      (node (ref "J1") (pin "15") (pinfunction "15_15") (pintype "passive"))
      (node (ref "R25") (pin "2") (pinfunction "2_2") (pintype "passive"))
      (node (ref "R36") (pin "2") (pinfunction "2_2") (pintype "passive"))
    )
    (net (code "29") (name "Net-(J1-Pad16)") (class "Default")
      (node (ref "J1") (pin "16") (pinfunction "16_16") (pintype "passive"))
      (node (ref "R24") (pin "2") (pinfunction "2_2") (pintype "passive"))
    )
    (net (code "30") (name "Net-(R5-Pad2)") (class "Default")
      (node (ref "R5") (pin "2") (pinfunction "2_2") (pintype "passive"))
      (node (ref "X4") (pin "1") (pinfunction "1_1") (pintype "passive"))
    )
    (net (code "31") (name "Net-(R7-Pad2)") (class "Default")
      (node (ref "R7") (pin "2") (pinfunction "2_2") (pintype "passive"))
      (node (ref "X5") (pin "4") (pinfunction "4_4") (pintype "passive"))
    )
    (net (code "32") (name "Net-(TP1-s)") (class "Default")
      (node (ref "C14") (pin "1") (pinfunction "1_1") (pintype "passive"))
      (node (ref "R4") (pin "2") (pinfunction "2_2") (pintype "passive"))
      (node (ref "TP1") (pin "1") (pinfunction "s_1") (pintype "passive"))
      (node (ref "X5") (pin "1") (pinfunction "1_1") (pintype "passive"))
    )
    (net (code "33") (name "Net-(TP3-s)") (class "Default")
      (node (ref "R22") (pin "2") (pinfunction "2_2") (pintype "passive"))
      (node (ref "TP3") (pin "1") (pinfunction "s_1") (pintype "passive"))
      (node (ref "X6") (pin "1") (pinfunction "1_1") (pintype "passive"))
    )
    (net (code "34") (name "Net-(TP4-s)") (class "Default")
      (node (ref "C38") (pin "1") (pinfunction "1_1") (pintype "passive"))
      (node (ref "J1") (pin "1") (pinfunction "1_1") (pintype "passive"))
      (node (ref "J1") (pin "2") (pinfunction "2_2") (pintype "passive"))
      (node (ref "J1") (pin "3") (pinfunction "3_3") (pintype "passive"))
      (node (ref "R28") (pin "2") (pinfunction "2_2") (pintype "passive"))
      (node (ref "R34") (pin "2") (pinfunction "2_2") (pintype "passive"))
      (node (ref "TP4") (pin "1") (pinfunction "s_1") (pintype "passive"))
      (node (ref "VT1") (pin "2") (pinfunction "Collector_2") (pintype "passive"))
    )
    (net (code "35") (name "Net-(VD1-Anode)") (class "Default")
      (node (ref "R6") (pin "1") (pinfunction "1_1") (pintype "passive"))
      (node (ref "VD1") (pin "2") (pinfunction "Anode_2") (pintype "passive"))
    )
    (net (code "36") (name "Net-(VT1-Base)") (class "Default")
      (node (ref "C38") (pin "2") (pinfunction "2_2") (pintype "passive"))
      (node (ref "R32") (pin "1") (pinfunction "1_1") (pintype "passive"))
      (node (ref "VT1") (pin "3") (pinfunction "Base_3") (pintype "passive"))
      (node (ref "VT2") (pin "3") (pinfunction "Collector_3") (pintype "passive"))
      (node (ref "VT3") (pin "3") (pinfunction "Base_3") (pintype "passive"))
    )
    (net (code "37") (name "Net-(VT1-Emitter)") (class "Default")
      (node (ref "J2") (pin "1") (pinfunction "1_1") (pintype "passive"))
      (node (ref "R27") (pin "1") (pinfunction "1_1") (pintype "passive"))
      (node (ref "VT1") (pin "1") (pinfunction "Emitter_1") (pintype "passive"))
    )
    (net (code "38") (name "Net-(VT2-base)") (class "Default")
      (node (ref "R31") (pin "1") (pinfunction "1_1") (pintype "passive"))
      (node (ref "R35") (pin "2") (pinfunction "2_2") (pintype "passive"))
      (node (ref "VT2") (pin "1") (pinfunction "base_1") (pintype "passive"))
    )
    (net (code "39") (name "Net-(VT3-Collector)") (class "Default")
      (node (ref "VT3") (pin "2") (pinfunction "Collector_2") (pintype "passive"))
      (node (ref "X7") (pin "1") (pinfunction "1_1") (pintype "passive"))
    )
    (net (code "40") (name "Net-(VT3-Emitter)") (class "Default")
      (node (ref "J3") (pin "1") (pinfunction "1_1") (pintype "passive"))
      (node (ref "R33") (pin "1") (pinfunction "1_1") (pintype "passive"))
      (node (ref "VT3") (pin "1") (pinfunction "Emitter_1") (pintype "passive"))
    )
    (net (code "41") (name "Net-(X3B-VBUS-PadA4)") (class "Default")
      (node (ref "X3") (pin "A4") (pinfunction "VBUS_A4") (pintype "power_in"))
      (node (ref "X3") (pin "A9") (pinfunction "VBUS_A9") (pintype "power_in"))
      (node (ref "X3") (pin "B4") (pinfunction "VBUS_B4") (pintype "power_in"))
      (node (ref "X3") (pin "B9") (pinfunction "VBUS_B9") (pintype "power_in"))
      (node (ref "X4") (pin "4") (pinfunction "4_4") (pintype "passive"))
    )
    (net (code "42") (name "unconnected-(DA2-SYNCIN-Pad14)") (class "Default")
      (node (ref "DA2") (pin "14") (pinfunction "SYNCIN_14") (pintype "input+no_connect"))
    )
    (net (code "43") (name "unconnected-(DA2-SYNCOUT-Pad8)") (class "Default")
      (node (ref "DA2") (pin "8") (pinfunction "SYNCOUT_8") (pintype "output+no_connect"))
    )
    (net (code "44") (name "unconnected-(R16-Pad1)") (class "Default")
      (node (ref "R16") (pin "1") (pinfunction "1_1") (pintype "passive+no_connect"))
    )
    (net (code "45") (name "unconnected-(R23-Pad2)") (class "Default")
      (node (ref "R23") (pin "2") (pinfunction "2_2") (pintype "passive+no_connect"))
    )
    (net (code "46") (name "unconnected-(VT4-Collector-Pad3)") (class "Default")
      (node (ref "VT4") (pin "3") (pinfunction "Collector_3") (pintype "passive"))
    )
    (net (code "47") (name "unconnected-(VT4-Emitter-Pad2)") (class "Default")
      (node (ref "VT4") (pin "2") (pinfunction "Emitter_2") (pintype "passive"))
    )
    (net (code "48") (name "unconnected-(VT4-base-Pad1)") (class "Default")
      (node (ref "VT4") (pin "1") (pinfunction "base_1") (pintype "passive"))
    )
    (net (code "49") (name "unconnected-(VT5-Collector-Pad3)") (class "Default")
      (node (ref "VT5") (pin "3") (pinfunction "Collector_3") (pintype "passive"))
    )
    (net (code "50") (name "unconnected-(VT5-Emitter-Pad2)") (class "Default")
      (node (ref "VT5") (pin "2") (pinfunction "Emitter_2") (pintype "passive"))
    )
    (net (code "51") (name "unconnected-(VT5-base-Pad1)") (class "Default")
      (node (ref "VT5") (pin "1") (pinfunction "base_1") (pintype "passive"))
    )
    (net (code "52") (name "unconnected-(VT6-Collector-Pad3)") (class "Default")
      (node (ref "VT6") (pin "3") (pinfunction "Collector_3") (pintype "passive"))
    )
    (net (code "53") (name "unconnected-(VT6-Emitter-Pad2)") (class "Default")
      (node (ref "VT6") (pin "2") (pinfunction "Emitter_2") (pintype "passive"))
    )
    (net (code "54") (name "unconnected-(VT6-base-Pad1)") (class "Default")
      (node (ref "VT6") (pin "1") (pinfunction "base_1") (pintype "passive"))
    )
    (net (code "55") (name "unconnected-(VT7-Collector-Pad3)") (class "Default")
      (node (ref "VT7") (pin "3") (pinfunction "Collector_3") (pintype "passive"))
    )
    (net (code "56") (name "unconnected-(VT7-Emitter-Pad2)") (class "Default")
      (node (ref "VT7") (pin "2") (pinfunction "Emitter_2") (pintype "passive"))
    )
    (net (code "57") (name "unconnected-(VT7-base-Pad1)") (class "Default")
      (node (ref "VT7") (pin "1") (pinfunction "base_1") (pintype "passive"))
    )
    (net (code "58") (name "unconnected-(X3A-CC1-PadA5)") (class "Default")
      (node (ref "X3") (pin "A5") (pinfunction "CC1_A5") (pintype "bidirectional+no_connect"))
    )
    (net (code "59") (name "unconnected-(X3A-CC2-PadB5)") (class "Default")
      (node (ref "X3") (pin "B5") (pinfunction "CC2_B5") (pintype "bidirectional+no_connect"))
    )
    (net (code "60") (name "unconnected-(X3A-DN1-PadA7)") (class "Default")
      (node (ref "X3") (pin "A7") (pinfunction "DN1_A7") (pintype "bidirectional+no_connect"))
    )
    (net (code "61") (name "unconnected-(X3A-DN2-PadB7)") (class "Default")
      (node (ref "X3") (pin "B7") (pinfunction "DN2_B7") (pintype "bidirectional+no_connect"))
    )
    (net (code "62") (name "unconnected-(X3A-DP1-PadA6)") (class "Default")
      (node (ref "X3") (pin "A6") (pinfunction "DP1_A6") (pintype "bidirectional+no_connect"))
    )
    (net (code "63") (name "unconnected-(X3A-DP2-PadB6)") (class "Default")
      (node (ref "X3") (pin "B6") (pinfunction "DP2_B6") (pintype "bidirectional+no_connect"))
    )
    (net (code "64") (name "unconnected-(X3A-SBU1-PadA8)") (class "Default")
      (node (ref "X3") (pin "A8") (pinfunction "SBU1_A8") (pintype "bidirectional+no_connect"))
    )
    (net (code "65") (name "unconnected-(X3A-SBU2-PadB8)") (class "Default")
      (node (ref "X3") (pin "B8") (pinfunction "SBU2_B8") (pintype "bidirectional+no_connect"))
    )
    (net (code "66") (name "unconnected-(X3A-SSRXN1-PadB10)") (class "Default")
      (node (ref "X3") (pin "B10") (pinfunction "SSRXN1_B10") (pintype "bidirectional+no_connect"))
    )
    (net (code "67") (name "unconnected-(X3A-SSRXN2-PadA10)") (class "Default")
      (node (ref "X3") (pin "A10") (pinfunction "SSRXN2_A10") (pintype "bidirectional+no_connect"))
    )
    (net (code "68") (name "unconnected-(X3A-SSRXP1-PadB11)") (class "Default")
      (node (ref "X3") (pin "B11") (pinfunction "SSRXP1_B11") (pintype "bidirectional+no_connect"))
    )
    (net (code "69") (name "unconnected-(X3A-SSRXP2-PadA11)") (class "Default")
      (node (ref "X3") (pin "A11") (pinfunction "SSRXP2_A11") (pintype "bidirectional+no_connect"))
    )
    (net (code "70") (name "unconnected-(X3A-SSTXN1-PadA3)") (class "Default")
      (node (ref "X3") (pin "A3") (pinfunction "SSTXN1_A3") (pintype "bidirectional+no_connect"))
    )
    (net (code "71") (name "unconnected-(X3A-SSTXN2-PadB3)") (class "Default")
      (node (ref "X3") (pin "B3") (pinfunction "SSTXN2_B3") (pintype "bidirectional+no_connect"))
    )
    (net (code "72") (name "unconnected-(X3A-SSTXP1-PadA2)") (class "Default")
      (node (ref "X3") (pin "A2") (pinfunction "SSTXP1_A2") (pintype "bidirectional+no_connect"))
    )
    (net (code "73") (name "unconnected-(X3A-SSTXP2-PadB2)") (class "Default")
      (node (ref "X3") (pin "B2") (pinfunction "SSTXP2_B2") (pintype "bidirectional+no_connect"))
    )
  )
)
